# SCore-SR1_2024-11-09.net
KiCad netlist of a schematic drawn in Altium Designer
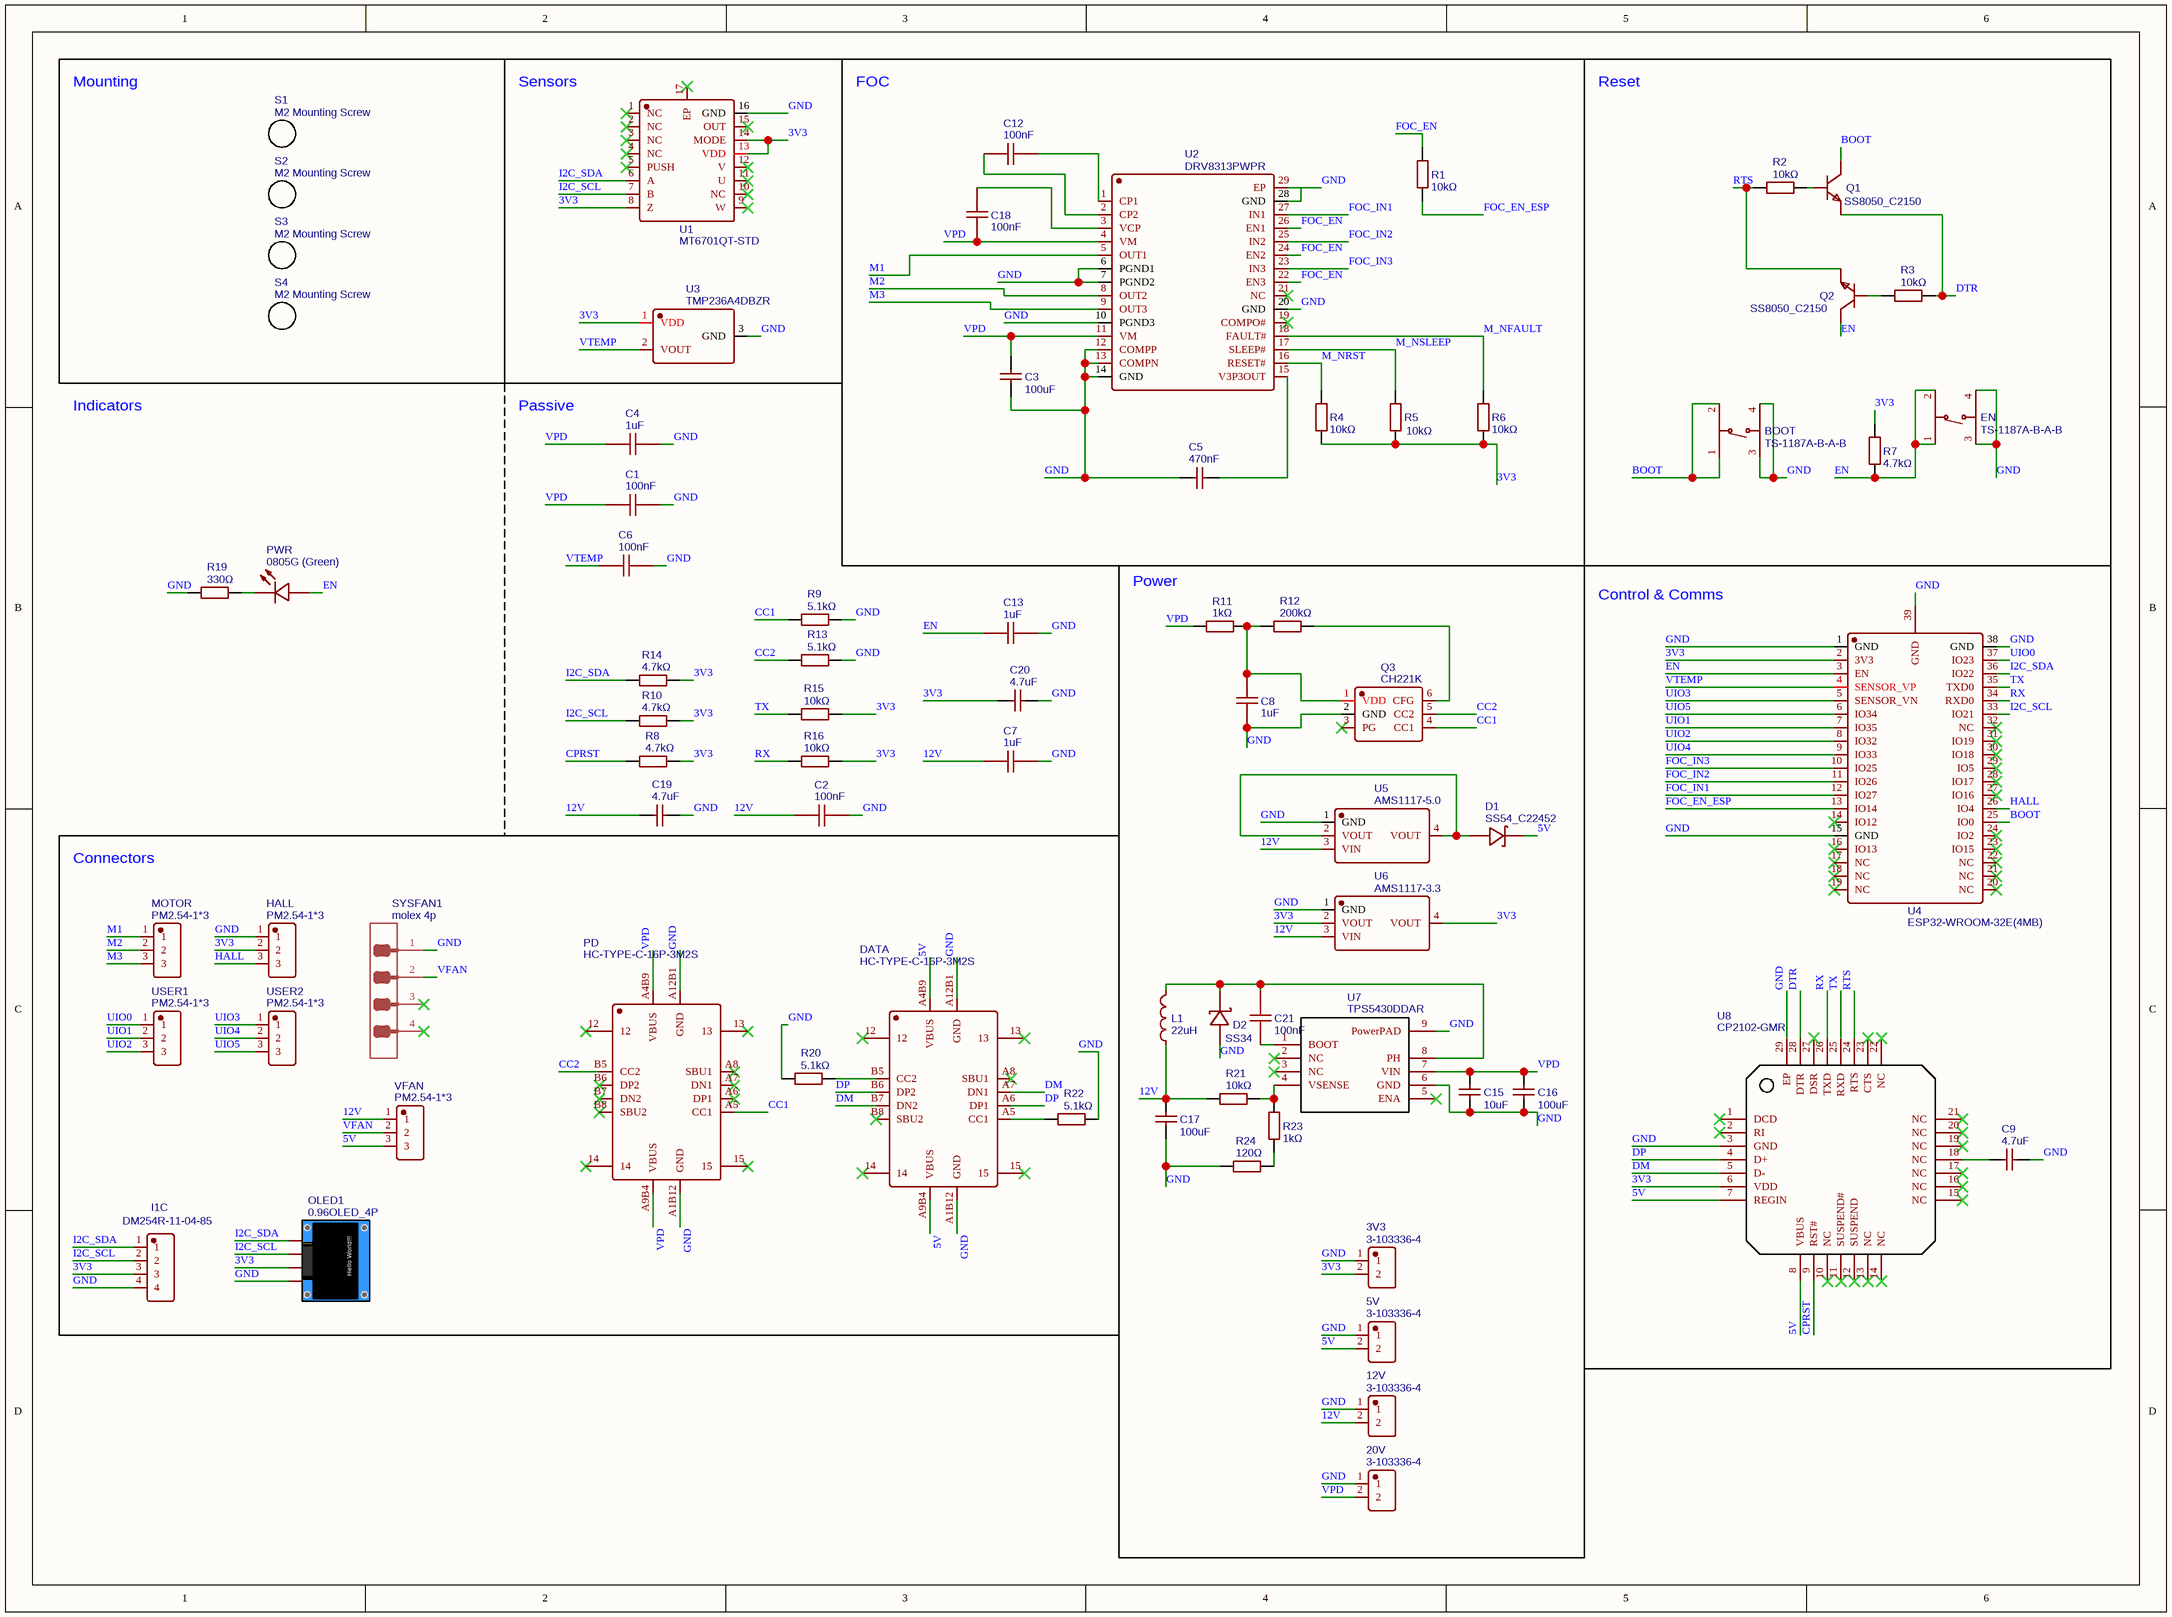
[diagram p0: SCore-SR1_2024-11-09.schdoc]

(export (version "E")
  (design (tool "Eeschema 10.0.6"))
  (components
    (comp (ref "3V3")
      (value "3-103336-4")
      (fields (field (name "MANUFACTURER") "TE Connectivity(泰科电子)") (field (name "CONTRIBUTOR") "lcsc"))
      (libsource (lib "altium-import") (part "root_0_3-103336-4_"))
    )
    (comp (ref "5V")
      (value "3-103336-4")
      (fields (field (name "MANUFACTURER") "TE Connectivity(泰科电子)") (field (name "CONTRIBUTOR") "lcsc"))
      (libsource (lib "altium-import") (part "root_0_3-103336-4_"))
    )
    (comp (ref "12V")
      (value "3-103336-4")
      (fields (field (name "MANUFACTURER") "TE Connectivity(泰科电子)") (field (name "CONTRIBUTOR") "lcsc"))
      (libsource (lib "altium-import") (part "root_0_3-103336-4_"))
    )
    (comp (ref "20V")
      (value "3-103336-4")
      (fields (field (name "MANUFACTURER") "TE Connectivity(泰科电子)") (field (name "CONTRIBUTOR") "lcsc"))
      (libsource (lib "altium-import") (part "root_0_3-103336-4_"))
    )
    (comp (ref "BOOT")
      (value "TS-1187A-B-A-B")
      (fields (field (name "MANUFACTURER") "XKB Connectivity(中国星坤)") (field (name "CONTRIBUTOR") "LCSC"))
      (libsource (lib "altium-import") (part "root_1_TS-1187A-B-A-B_"))
    )
    (comp (ref "C1")
      (value "100nF")
      (fields
        (field (name "MANUFACTURER") "YAGEO(国巨)")
        (field (name "MANUFACTURER PART") "CC0603KRX7R9BB104")
      )
      (libsource (lib "altium-import") (part "root_0_100nF_"))
    )
    (comp (ref "C2")
      (value "100nF")
      (fields
        (field (name "MANUFACTURER") "YAGEO(国巨)")
        (field (name "MANUFACTURER PART") "CC0603KRX7R9BB104")
      )
      (libsource (lib "altium-import") (part "root_0_100nF_"))
    )
    (comp (ref "C3")
      (value "100uF")
      (fields
        (field (name "MANUFACTURER PART") "CL31A107MQHNNNE")
        (field (name "MANUFACTURER") "SAMSUNG(三星)")
      )
      (libsource (lib "altium-import") (part "root_1_100uF_"))
    )
    (comp (ref "C4")
      (value "1uF")
      (fields
        (field (name "MANUFACTURER PART") "CL10A105KB8NNNC")
        (field (name "MANUFACTURER") "SAMSUNG(三星)")
      )
      (libsource (lib "altium-import") (part "root_0_1uF_"))
    )
    (comp (ref "C5")
      (value "470nF")
      (fields
        (field (name "MANUFACTURER PART") "CL21B474KBFNNNE")
        (field (name "MANUFACTURER") "SAMSUNG(三星)")
        (field (name "CONTRIBUTOR") "eisendev")
      )
      (libsource (lib "altium-import") (part "root_3_470nF_"))
    )
    (comp (ref "C6")
      (value "100nF")
      (fields
        (field (name "MANUFACTURER") "YAGEO(国巨)")
        (field (name "MANUFACTURER PART") "CC0603KRX7R9BB104")
      )
      (libsource (lib "altium-import") (part "root_0_100nF_"))
    )
    (comp (ref "C7")
      (value "1uF")
      (fields
        (field (name "MANUFACTURER PART") "CL10A105KB8NNNC")
        (field (name "MANUFACTURER") "SAMSUNG(三星)")
      )
      (libsource (lib "altium-import") (part "root_0_1uF_"))
    )
    (comp (ref "C8")
      (value "1uF")
      (fields
        (field (name "MANUFACTURER PART") "CL10A105KB8NNNC")
        (field (name "MANUFACTURER") "SAMSUNG(三星)")
      )
      (libsource (lib "altium-import") (part "root_1_1uF_"))
    )
    (comp (ref "C9")
      (value "4.7uF")
      (fields
        (field (name "MANUFACTURER PART") "CL21A475KAQNNNE")
        (field (name "MANUFACTURER") "SAMSUNG(三星)")
      )
      (libsource (lib "altium-import") (part "root_0_4.7uF_"))
    )
    (comp (ref "C12")
      (value "100nF")
      (fields
        (field (name "MANUFACTURER") "YAGEO(国巨)")
        (field (name "MANUFACTURER PART") "CC0603KRX7R9BB104")
      )
      (libsource (lib "altium-import") (part "root_0_100nF_"))
    )
    (comp (ref "C13")
      (value "1uF")
      (fields
        (field (name "MANUFACTURER PART") "CL10A105KB8NNNC")
        (field (name "MANUFACTURER") "SAMSUNG(三星)")
      )
      (libsource (lib "altium-import") (part "root_0_1uF_"))
    )
    (comp (ref "C15")
      (value "10uF")
      (fields
        (field (name "MANUFACTURER PART") "CL31A106KBHNNNE")
        (field (name "MANUFACTURER") "SAMSUNG(三星)")
      )
      (libsource (lib "altium-import") (part "root_1_10uF_"))
    )
    (comp (ref "C16")
      (value "100uF")
      (fields
        (field (name "MANUFACTURER PART") "CL31A107MQHNNNE")
        (field (name "MANUFACTURER") "SAMSUNG(三星)")
      )
      (libsource (lib "altium-import") (part "root_1_100uF_"))
    )
    (comp (ref "C17")
      (value "100uF")
      (fields
        (field (name "MANUFACTURER PART") "CL31A107MQHNNNE")
        (field (name "MANUFACTURER") "SAMSUNG(三星)")
      )
      (libsource (lib "altium-import") (part "root_1_100uF_"))
    )
    (comp (ref "C18")
      (value "100nF")
      (fields
        (field (name "MANUFACTURER") "YAGEO(国巨)")
        (field (name "MANUFACTURER PART") "CC0603KRX7R9BB104")
      )
      (libsource (lib "altium-import") (part "root_1_100nF_"))
    )
    (comp (ref "C19")
      (value "4.7uF")
      (fields
        (field (name "MANUFACTURER PART") "CL21A475KAQNNNE")
        (field (name "MANUFACTURER") "SAMSUNG(三星)")
      )
      (libsource (lib "altium-import") (part "root_0_4.7uF_"))
    )
    (comp (ref "C20")
      (value "4.7uF")
      (fields
        (field (name "MANUFACTURER PART") "CL21A475KAQNNNE")
        (field (name "MANUFACTURER") "SAMSUNG(三星)")
      )
      (libsource (lib "altium-import") (part "root_0_4.7uF_"))
    )
    (comp (ref "C21")
      (value "100nF")
      (fields
        (field (name "MANUFACTURER") "YAGEO(国巨)")
        (field (name "MANUFACTURER PART") "CC0603KRX7R9BB104")
      )
      (libsource (lib "altium-import") (part "root_3_100nF_"))
    )
    (comp (ref "D1")
      (value "SS54_C22452")
      (fields
        (field (name "MANUFACTURER PART") "SS54")
        (field (name "MANUFACTURER") "MDD")
        (field (name "CONTRIBUTOR") "mtz8302")
      )
      (libsource (lib "altium-import") (part "root_0_SS54_C22452_"))
    )
    (comp (ref "D2")
      (value "SS34")
      (fields (field (name "MANUFACTURER") "MDD(辰达半导体)"))
      (libsource (lib "altium-import") (part "root_3_SS34_"))
    )
    (comp (ref "DATA")
      (value "HC-TYPE-C-16P-3M2S")
      (fields (field (name "MANUFACTURER") "HC(虹成电子)") (field (name "CONTRIBUTOR") "lcsc"))
      (libsource (lib "altium-import") (part "root_0_HC-TYPE-C-16P-3M2S_"))
    )
    (comp (ref "EN")
      (value "TS-1187A-B-A-B")
      (fields (field (name "MANUFACTURER") "XKB Connectivity(中国星坤)") (field (name "CONTRIBUTOR") "LCSC"))
      (libsource (lib "altium-import") (part "root_1_TS-1187A-B-A-B_"))
    )
    (comp (ref "HALL")
      (value "PM2.54-1*3")
      (fields (field (name "MANUFACTURER") "ZHOURI(洲日)") (field (name "CONTRIBUTOR") "lcsc"))
      (libsource (lib "altium-import") (part "root_0_PM2.54-1*3_"))
    )
    (comp (ref "I1C")
      (value "DM254R-11-04-85")
      (fields (field (name "MANUFACTURER") "DEALON(德艺隆)") (field (name "CONTRIBUTOR") "LCSC"))
      (libsource (lib "altium-import") (part "root_0_DM254R-11-04-85_"))
    )
    (comp (ref "L1")
      (value "22uH")
      (fields (field (name "MANUFACTURER") "FH(风华)") (field (name "MANUFACTURER PART") "PRS4018-220MT"))
      (libsource (lib "altium-import") (part "root_1_22uH_"))
    )
    (comp (ref "MOTOR")
      (value "PM2.54-1*3")
      (fields (field (name "MANUFACTURER") "ZHOURI(洲日)") (field (name "CONTRIBUTOR") "lcsc"))
      (libsource (lib "altium-import") (part "root_0_PM2.54-1*3_"))
    )
    (comp (ref "OLED1")
      (value "0.96OLED_4P")
      (fields (field (name "CONTRIBUTOR") "LCEDA_Lib"))
      (libsource (lib "altium-import") (part "root_3_0.96OLED_4P_"))
    )
    (comp (ref "PD")
      (value "HC-TYPE-C-16P-3M2S")
      (fields (field (name "MANUFACTURER") "HC(虹成电子)") (field (name "CONTRIBUTOR") "lcsc"))
      (libsource (lib "altium-import") (part "root_0_HC-TYPE-C-16P-3M2S_"))
    )
    (comp (ref "PWR")
      (value "0805G (Green)")
      (fields (field (name "MANUFACTURER") "KENTO") (field (name "MANUFACTURER PART") "KT-0805G"))
      (libsource (lib "altium-import") (part "root_0_0805G (Green)_"))
    )
    (comp (ref "Q1")
      (value "SS8050_C2150")
      (fields (field (name "MANUFACTURER") "CJ(江苏长电/长晶)") (field (name "MANUFACTURER PART") "SS8050"))
      (libsource (lib "altium-import") (part "root_0_SS8050_C2150_"))
    )
    (comp (ref "Q2")
      (value "SS8050_C2150")
      (fields (field (name "MANUFACTURER") "CJ(江苏长电/长晶)") (field (name "MANUFACTURER PART") "SS8050"))
      (libsource (lib "altium-import") (part "root_2_SS8050_C2150_"))
    )
    (comp (ref "Q3")
      (value "CH221K")
      (fields (field (name "CONTRIBUTOR") "lcsc"))
      (libsource (lib "altium-import") (part "root_0_CH221K_"))
    )
    (comp (ref "R1")
      (value "10kΩ")
      (fields (field (name "MANUFACTURER") "UniOhm") (field (name "MANUFACTURER PART") "0603WAF4701T5E"))
      (libsource (lib "altium-import") (part "root_1_10kΩ_"))
    )
    (comp (ref "R2")
      (value "10kΩ")
      (fields
        (field (name "MANUFACTURER") "UNI-ROYAL(厚声)")
        (field (name "MANUFACTURER PART") "1206W4F1002T5E")
      )
      (libsource (lib "altium-import") (part "root_0_10kΩ_"))
    )
    (comp (ref "R3")
      (value "10kΩ")
      (fields
        (field (name "MANUFACTURER") "UNI-ROYAL(厚声)")
        (field (name "MANUFACTURER PART") "1206W4F1002T5E")
      )
      (libsource (lib "altium-import") (part "root_0_10kΩ_"))
    )
    (comp (ref "R4")
      (value "10kΩ")
      (fields (field (name "MANUFACTURER") "UniOhm") (field (name "MANUFACTURER PART") "0603WAF4701T5E"))
      (libsource (lib "altium-import") (part "root_1_10kΩ_"))
    )
    (comp (ref "R5")
      (value "10kΩ")
      (fields (field (name "MANUFACTURER") "UniOhm") (field (name "MANUFACTURER PART") "0603WAF4701T5E"))
      (libsource (lib "altium-import") (part "root_1_10kΩ_"))
    )
    (comp (ref "R6")
      (value "10kΩ")
      (fields (field (name "MANUFACTURER") "UniOhm") (field (name "MANUFACTURER PART") "0603WAF4701T5E"))
      (libsource (lib "altium-import") (part "root_1_10kΩ_"))
    )
    (comp (ref "R7")
      (value "4.7kΩ")
      (fields
        (field (name "MANUFACTURER") "UNI-ROYAL(厚声)")
        (field (name "MANUFACTURER PART") "0805W8F4701T5E")
      )
      (libsource (lib "altium-import") (part "root_1_4.7kΩ_"))
    )
    (comp (ref "R8")
      (value "4.7kΩ")
      (fields
        (field (name "MANUFACTURER") "UNI-ROYAL(厚声)")
        (field (name "MANUFACTURER PART") "0805W8F4701T5E")
      )
      (libsource (lib "altium-import") (part "root_2_4.7kΩ_"))
    )
    (comp (ref "R9")
      (value "5.1kΩ")
      (fields
        (field (name "MANUFACTURER PART") "0603WAF5101T5E")
        (field (name "MANUFACTURER") "UNI-ROYAL(厚声)")
      )
      (libsource (lib "altium-import") (part "root_0_5.1kΩ_"))
    )
    (comp (ref "R10")
      (value "4.7kΩ")
      (fields
        (field (name "MANUFACTURER") "UNI-ROYAL(厚声)")
        (field (name "MANUFACTURER PART") "0805W8F4701T5E")
      )
      (libsource (lib "altium-import") (part "root_2_4.7kΩ_"))
    )
    (comp (ref "R11")
      (value "1kΩ")
      (fields
        (field (name "MANUFACTURER") "UNI-ROYAL(厚声)")
        (field (name "MANUFACTURER PART") "0402WGF1001TCE")
      )
      (libsource (lib "altium-import") (part "root_0_1kΩ_"))
    )
    (comp (ref "R12")
      (value "200kΩ")
      (fields
        (field (name "MANUFACTURER") "UNI-ROYAL(厚声)")
        (field (name "MANUFACTURER PART") "0805W8F2003T5E")
      )
      (libsource (lib "altium-import") (part "root_0_200kΩ_"))
    )
    (comp (ref "R13")
      (value "5.1kΩ")
      (fields
        (field (name "MANUFACTURER PART") "0603WAF5101T5E")
        (field (name "MANUFACTURER") "UNI-ROYAL(厚声)")
      )
      (libsource (lib "altium-import") (part "root_0_5.1kΩ_"))
    )
    (comp (ref "R14")
      (value "4.7kΩ")
      (fields
        (field (name "MANUFACTURER") "UNI-ROYAL(厚声)")
        (field (name "MANUFACTURER PART") "0805W8F4701T5E")
      )
      (libsource (lib "altium-import") (part "root_2_4.7kΩ_"))
    )
    (comp (ref "R15")
      (value "10kΩ")
      (fields (field (name "MANUFACTURER") "UniOhm") (field (name "MANUFACTURER PART") "0603WAF4701T5E"))
      (libsource (lib "altium-import") (part "root_2_10kΩ_"))
    )
    (comp (ref "R16")
      (value "10kΩ")
      (fields (field (name "MANUFACTURER") "UniOhm") (field (name "MANUFACTURER PART") "0603WAF4701T5E"))
      (libsource (lib "altium-import") (part "root_2_10kΩ_"))
    )
    (comp (ref "R19")
      (value "330Ω")
      (fields
        (field (name "MANUFACTURER") "UNI-ROYAL(厚声)")
        (field (name "MANUFACTURER PART") "0805W8F3300T5E")
      )
      (libsource (lib "altium-import") (part "root_0_330Ω_"))
    )
    (comp (ref "R20")
      (value "5.1kΩ")
      (fields
        (field (name "MANUFACTURER PART") "0603WAF5101T5E")
        (field (name "MANUFACTURER") "UNI-ROYAL(厚声)")
      )
      (libsource (lib "altium-import") (part "root_0_5.1kΩ_"))
    )
    (comp (ref "R21")
      (value "10kΩ")
      (fields
        (field (name "MANUFACTURER") "UNI-ROYAL(厚声)")
        (field (name "MANUFACTURER PART") "0805W8F1002T5E")
      )
      (libsource (lib "altium-import") (part "root_2_10kΩ_"))
    )
    (comp (ref "R22")
      (value "5.1kΩ")
      (fields
        (field (name "MANUFACTURER PART") "0603WAF5101T5E")
        (field (name "MANUFACTURER") "UNI-ROYAL(厚声)")
      )
      (libsource (lib "altium-import") (part "root_0_5.1kΩ_"))
    )
    (comp (ref "R23")
      (value "1kΩ")
      (fields
        (field (name "MANUFACTURER") "UNI-ROYAL(厚声)")
        (field (name "MANUFACTURER PART") "0402WGF1001TCE")
      )
      (libsource (lib "altium-import") (part "root_1_1kΩ_"))
    )
    (comp (ref "R24")
      (value "120Ω")
      (fields
        (field (name "MANUFACTURER") "UNI-ROYAL(厚声)")
        (field (name "MANUFACTURER PART") "0805W8F1200T5E")
      )
      (libsource (lib "altium-import") (part "root_0_120Ω_"))
    )
    (comp (ref "S1")
      (value "M2 Mounting Screw")
      (fields (field (name "CONTRIBUTOR") "Dayat -"))
      (libsource (lib "altium-import") (part "root_0_M2 Mounting Screw_"))
    )
    (comp (ref "S2")
      (value "M2 Mounting Screw")
      (fields (field (name "CONTRIBUTOR") "Dayat -"))
      (libsource (lib "altium-import") (part "root_0_M2 Mounting Screw_"))
    )
    (comp (ref "S3")
      (value "M2 Mounting Screw")
      (fields (field (name "CONTRIBUTOR") "Dayat -"))
      (libsource (lib "altium-import") (part "root_0_M2 Mounting Screw_"))
    )
    (comp (ref "S4")
      (value "M2 Mounting Screw")
      (fields (field (name "CONTRIBUTOR") "Dayat -"))
      (libsource (lib "altium-import") (part "root_0_M2 Mounting Screw_"))
    )
    (comp (ref "SYSFAN1")
      (value "molex 4p")
      (fields (field (name "CONTRIBUTOR") "delil1220"))
      (libsource (lib "altium-import") (part "root_0_molex 4p_"))
    )
    (comp (ref "U1")
      (value "MT6701QT-STD")
      (fields (field (name "MANUFACTURER") "MagnTek(麦歌恩)") (field (name "CONTRIBUTOR") "LCSC"))
      (libsource (lib "altium-import") (part "root_0_MT6701QT-STD_"))
    )
    (comp (ref "U2")
      (value "DRV8313PWPR")
      (fields (field (name "MANUFACTURER") "Texas Instruments") (field (name "CONTRIBUTOR") "LCSC"))
      (libsource (lib "altium-import") (part "root_0_DRV8313PWPR_"))
    )
    (comp (ref "U3")
      (value "TMP236A4DBZR")
      (fields (field (name "MANUFACTURER") "TI(德州仪器)") (field (name "CONTRIBUTOR") "LCSC"))
      (libsource (lib "altium-import") (part "root_0_TMP236A4DBZR_"))
    )
    (comp (ref "U4")
      (value "ESP32-WROOM-32E(4MB)")
      (fields
        (field (name "MANUFACTURER") "ESPRESSIF(乐鑫)")
        (field (name "MANUFACTURER PART") "ESP32-WROOM-32E-N4")
        (field (name "CONTRIBUTOR") "LCSC")
      )
      (libsource (lib "altium-import") (part "root_0_ESP32-WROOM-32E(4MB)_"))
    )
    (comp (ref "U5")
      (value "AMS1117-5.0")
      (fields (field (name "MANUFACTURER") "AMS"))
      (libsource (lib "altium-import") (part "root_0_AMS1117-5.0_"))
    )
    (comp (ref "U6")
      (value "AMS1117-3.3")
      (fields (field (name "MANUFACTURER") "AMS"))
      (libsource (lib "altium-import") (part "root_0_AMS1117-3.3_"))
    )
    (comp (ref "U7")
      (value "TPS5430DDAR")
      (fields (field (name "MANUFACTURER") "TI(德州仪器)"))
      (libsource (lib "altium-import") (part "root_0_TPS5430DDAR_"))
    )
    (comp (ref "U8")
      (value "CP2102-GMR")
      (fields (field (name "MANUFACTURER") "SKYWORKS/SILICON LABS(芯科)"))
      (libsource (lib "altium-import") (part "root_0_CP2102-GMR_"))
    )
    (comp (ref "USER1")
      (value "PM2.54-1*3")
      (fields (field (name "MANUFACTURER") "ZHOURI(洲日)") (field (name "CONTRIBUTOR") "lcsc"))
      (libsource (lib "altium-import") (part "root_0_PM2.54-1*3_"))
    )
    (comp (ref "USER2")
      (value "PM2.54-1*3")
      (fields (field (name "MANUFACTURER") "ZHOURI(洲日)") (field (name "CONTRIBUTOR") "lcsc"))
      (libsource (lib "altium-import") (part "root_0_PM2.54-1*3_"))
    )
    (comp (ref "VFAN")
      (value "PM2.54-1*3")
      (fields (field (name "MANUFACTURER") "ZHOURI(洲日)") (field (name "CONTRIBUTOR") "lcsc"))
      (libsource (lib "altium-import") (part "root_0_PM2.54-1*3_"))
    )
  )
  (nets
    (net (code "1") (name "/3V3") (class "Default")
      (node (ref "3V3") (pin "2") (pinfunction "2_2") (pintype "passive"))
      (node (ref "C20") (pin "1") (pinfunction "1_1") (pintype "passive"))
      (node (ref "HALL") (pin "2") (pinfunction "2_2") (pintype "passive"))
      (node (ref "I1C") (pin "3") (pinfunction "3_3") (pintype "passive"))
      (node (ref "OLED1") (pin "3") (pinfunction "3_3") (pintype "passive"))
      (node (ref "R10") (pin "1") (pinfunction "1_1") (pintype "passive"))
      (node (ref "R14") (pin "1") (pinfunction "1_1") (pintype "passive"))
      (node (ref "R15") (pin "1") (pinfunction "1_1") (pintype "passive"))
      (node (ref "R16") (pin "1") (pinfunction "1_1") (pintype "passive"))
      (node (ref "R4") (pin "1") (pinfunction "1_1") (pintype "passive"))
      (node (ref "R5") (pin "1") (pinfunction "1_1") (pintype "passive"))
      (node (ref "R6") (pin "1") (pinfunction "1_1") (pintype "passive"))
      (node (ref "R7") (pin "2") (pinfunction "2_2") (pintype "passive"))
      (node (ref "R8") (pin "1") (pinfunction "1_1") (pintype "passive"))
      (node (ref "U1") (pin "13") (pinfunction "VDD_13") (pintype "passive"))
      (node (ref "U1") (pin "14") (pinfunction "MODE_14") (pintype "passive"))
      (node (ref "U1") (pin "8") (pinfunction "Z_8") (pintype "passive"))
      (node (ref "U3") (pin "1") (pinfunction "VDD_1") (pintype "passive"))
      (node (ref "U4") (pin "2") (pinfunction "3V3_2") (pintype "passive"))
      (node (ref "U6") (pin "2") (pinfunction "VOUT_2") (pintype "passive"))
      (node (ref "U6") (pin "4") (pinfunction "VOUT_4") (pintype "passive"))
      (node (ref "U8") (pin "6") (pinfunction "VDD_6") (pintype "passive"))
    )
    (net (code "2") (name "/5V") (class "Default")
      (node (ref "5V") (pin "2") (pinfunction "2_2") (pintype "passive"))
      (node (ref "D1") (pin "2") (pinfunction "K_2") (pintype "passive"))
      (node (ref "DATA") (pin "A4B9") (pinfunction "VBUS_A4B9") (pintype "passive"))
      (node (ref "DATA") (pin "A9B4") (pinfunction "VBUS_A9B4") (pintype "passive"))
      (node (ref "U8") (pin "7") (pinfunction "REGIN_7") (pintype "passive"))
      (node (ref "U8") (pin "8") (pinfunction "VBUS_8") (pintype "passive"))
      (node (ref "VFAN") (pin "3") (pinfunction "3_3") (pintype "passive"))
    )
    (net (code "3") (name "/12V") (class "Default")
      (node (ref "12V") (pin "2") (pinfunction "2_2") (pintype "passive"))
      (node (ref "C17") (pin "2") (pinfunction "2_2") (pintype "passive"))
      (node (ref "C19") (pin "1") (pinfunction "1_1") (pintype "passive"))
      (node (ref "C2") (pin "1") (pinfunction "1_1") (pintype "passive"))
      (node (ref "C7") (pin "1") (pinfunction "1_1") (pintype "passive"))
      (node (ref "L1") (pin "1") (pinfunction "1_1") (pintype "passive"))
      (node (ref "R21") (pin "2") (pinfunction "2_2") (pintype "passive"))
      (node (ref "U5") (pin "3") (pinfunction "VIN_3") (pintype "passive"))
      (node (ref "U6") (pin "3") (pinfunction "VIN_3") (pintype "passive"))
      (node (ref "VFAN") (pin "1") (pinfunction "1_1") (pintype "passive"))
    )
    (net (code "4") (name "/BOOT") (class "Default")
      (node (ref "BOOT") (pin "1") (pinfunction "A_1") (pintype "passive"))
      (node (ref "BOOT") (pin "2") (pinfunction "B_2") (pintype "passive"))
      (node (ref "Q1") (pin "3") (pinfunction "C_3") (pintype "passive"))
      (node (ref "U4") (pin "25") (pinfunction "IO0_25") (pintype "passive"))
    )
    (net (code "5") (name "/CC1") (class "Default")
      (node (ref "PD") (pin "A5") (pinfunction "CC1_A5") (pintype "passive"))
      (node (ref "Q3") (pin "4") (pinfunction "CC1_4") (pintype "passive"))
      (node (ref "R9") (pin "1") (pinfunction "1_1") (pintype "passive"))
    )
    (net (code "6") (name "/CC2") (class "Default")
      (node (ref "PD") (pin "B5") (pinfunction "CC2_B5") (pintype "passive"))
      (node (ref "Q3") (pin "5") (pinfunction "CC2_5") (pintype "passive"))
      (node (ref "R13") (pin "1") (pinfunction "1_1") (pintype "passive"))
    )
    (net (code "7") (name "/CPRST") (class "Default")
      (node (ref "R8") (pin "2") (pinfunction "2_2") (pintype "passive"))
      (node (ref "U8") (pin "9") (pinfunction "RST#_9") (pintype "passive"))
    )
    (net (code "8") (name "/DM") (class "Default")
      (node (ref "DATA") (pin "A7") (pinfunction "DN1_A7") (pintype "passive"))
      (node (ref "DATA") (pin "B7") (pinfunction "DN2_B7") (pintype "passive"))
      (node (ref "U8") (pin "5") (pinfunction "D-_5") (pintype "passive"))
    )
    (net (code "9") (name "/DP") (class "Default")
      (node (ref "DATA") (pin "A6") (pinfunction "DP1_A6") (pintype "passive"))
      (node (ref "DATA") (pin "B6") (pinfunction "DP2_B6") (pintype "passive"))
      (node (ref "U8") (pin "4") (pinfunction "D+_4") (pintype "passive"))
    )
    (net (code "10") (name "/DTR") (class "Default")
      (node (ref "Q1") (pin "2") (pinfunction "E_2") (pintype "passive"))
      (node (ref "R3") (pin "2") (pinfunction "2_2") (pintype "passive"))
      (node (ref "U8") (pin "28") (pinfunction "DTR_28") (pintype "passive"))
    )
    (net (code "11") (name "/EN") (class "Default")
      (node (ref "C13") (pin "1") (pinfunction "1_1") (pintype "passive"))
      (node (ref "EN") (pin "1") (pinfunction "A_1") (pintype "passive"))
      (node (ref "EN") (pin "2") (pinfunction "B_2") (pintype "passive"))
      (node (ref "PWR") (pin "1") (pinfunction "A_1") (pintype "passive"))
      (node (ref "Q2") (pin "3") (pinfunction "C_3") (pintype "passive"))
      (node (ref "R7") (pin "1") (pinfunction "1_1") (pintype "passive"))
      (node (ref "U4") (pin "3") (pinfunction "EN_3") (pintype "passive"))
    )
    (net (code "12") (name "/FOC_EN") (class "Default")
      (node (ref "R1") (pin "2") (pinfunction "2_2") (pintype "passive"))
      (node (ref "U2") (pin "22") (pinfunction "EN3_22") (pintype "passive"))
      (node (ref "U2") (pin "24") (pinfunction "EN2_24") (pintype "passive"))
      (node (ref "U2") (pin "26") (pinfunction "EN1_26") (pintype "passive"))
    )
    (net (code "13") (name "/FOC_EN_ESP") (class "Default")
      (node (ref "R1") (pin "1") (pinfunction "1_1") (pintype "passive"))
      (node (ref "U4") (pin "13") (pinfunction "IO14_13") (pintype "passive"))
    )
    (net (code "14") (name "/FOC_IN1") (class "Default")
      (node (ref "U2") (pin "27") (pinfunction "IN1_27") (pintype "passive"))
      (node (ref "U4") (pin "12") (pinfunction "IO27_12") (pintype "passive"))
    )
    (net (code "15") (name "/FOC_IN2") (class "Default")
      (node (ref "U2") (pin "25") (pinfunction "IN2_25") (pintype "passive"))
      (node (ref "U4") (pin "11") (pinfunction "IO26_11") (pintype "passive"))
    )
    (net (code "16") (name "/FOC_IN3") (class "Default")
      (node (ref "U2") (pin "23") (pinfunction "IN3_23") (pintype "passive"))
      (node (ref "U4") (pin "10") (pinfunction "IO25_10") (pintype "passive"))
    )
    (net (code "17") (name "/GND") (class "Default")
      (node (ref "12V") (pin "1") (pinfunction "1_1") (pintype "passive"))
      (node (ref "20V") (pin "1") (pinfunction "1_1") (pintype "passive"))
      (node (ref "3V3") (pin "1") (pinfunction "1_1") (pintype "passive"))
      (node (ref "5V") (pin "1") (pinfunction "1_1") (pintype "passive"))
      (node (ref "BOOT") (pin "3") (pinfunction "C_3") (pintype "passive"))
      (node (ref "BOOT") (pin "4") (pinfunction "D_4") (pintype "passive"))
      (node (ref "C1") (pin "2") (pinfunction "2_2") (pintype "passive"))
      (node (ref "C13") (pin "2") (pinfunction "2_2") (pintype "passive"))
      (node (ref "C15") (pin "1") (pinfunction "1_1") (pintype "passive"))
      (node (ref "C16") (pin "1") (pinfunction "1_1") (pintype "passive"))
      (node (ref "C17") (pin "1") (pinfunction "1_1") (pintype "passive"))
      (node (ref "C19") (pin "2") (pinfunction "2_2") (pintype "passive"))
      (node (ref "C2") (pin "2") (pinfunction "2_2") (pintype "passive"))
      (node (ref "C20") (pin "2") (pinfunction "2_2") (pintype "passive"))
      (node (ref "C3") (pin "1") (pinfunction "1_1") (pintype "passive"))
      (node (ref "C4") (pin "2") (pinfunction "2_2") (pintype "passive"))
      (node (ref "C5") (pin "1") (pinfunction "1_1") (pintype "passive"))
      (node (ref "C6") (pin "2") (pinfunction "2_2") (pintype "passive"))
      (node (ref "C7") (pin "2") (pinfunction "2_2") (pintype "passive"))
      (node (ref "C8") (pin "1") (pinfunction "1_1") (pintype "passive"))
      (node (ref "C9") (pin "2") (pinfunction "2_2") (pintype "passive"))
      (node (ref "D2") (pin "2") (pinfunction "A_2") (pintype "passive"))
      (node (ref "DATA") (pin "A12B1") (pinfunction "GND_A12B1") (pintype "passive"))
      (node (ref "DATA") (pin "A1B12") (pinfunction "GND_A1B12") (pintype "passive"))
      (node (ref "EN") (pin "3") (pinfunction "C_3") (pintype "passive"))
      (node (ref "EN") (pin "4") (pinfunction "D_4") (pintype "passive"))
      (node (ref "HALL") (pin "1") (pinfunction "1_1") (pintype "passive"))
      (node (ref "I1C") (pin "4") (pinfunction "4_4") (pintype "passive"))
      (node (ref "OLED1") (pin "4") (pinfunction "4_4") (pintype "passive"))
      (node (ref "PD") (pin "A12B1") (pinfunction "GND_A12B1") (pintype "passive"))
      (node (ref "PD") (pin "A1B12") (pinfunction "GND_A1B12") (pintype "passive"))
      (node (ref "Q3") (pin "2") (pinfunction "GND_2") (pintype "passive"))
      (node (ref "R13") (pin "2") (pinfunction "2_2") (pintype "passive"))
      (node (ref "R19") (pin "1") (pinfunction "1_1") (pintype "passive"))
      (node (ref "R20") (pin "1") (pinfunction "1_1") (pintype "passive"))
      (node (ref "R22") (pin "2") (pinfunction "2_2") (pintype "passive"))
      (node (ref "R24") (pin "1") (pinfunction "1_1") (pintype "passive"))
      (node (ref "R9") (pin "2") (pinfunction "2_2") (pintype "passive"))
      (node (ref "SYSFAN1") (pin "1") (pinfunction "1_1") (pintype "passive"))
      (node (ref "U1") (pin "16") (pinfunction "GND_16") (pintype "passive"))
      (node (ref "U2") (pin "10") (pinfunction "PGND3_10") (pintype "passive"))
      (node (ref "U2") (pin "12") (pinfunction "COMPP_12") (pintype "passive"))
      (node (ref "U2") (pin "13") (pinfunction "COMPN_13") (pintype "passive"))
      (node (ref "U2") (pin "14") (pinfunction "GND_14") (pintype "passive"))
      (node (ref "U2") (pin "20") (pinfunction "GND_20") (pintype "passive"))
      (node (ref "U2") (pin "28") (pinfunction "GND_28") (pintype "passive"))
      (node (ref "U2") (pin "29") (pinfunction "EP_29") (pintype "passive"))
      (node (ref "U2") (pin "6") (pinfunction "PGND1_6") (pintype "passive"))
      (node (ref "U2") (pin "7") (pinfunction "PGND2_7") (pintype "passive"))
      (node (ref "U3") (pin "3") (pinfunction "GND_3") (pintype "passive"))
      (node (ref "U4") (pin "1") (pinfunction "GND_1") (pintype "passive"))
      (node (ref "U4") (pin "15") (pinfunction "GND_15") (pintype "passive"))
      (node (ref "U4") (pin "38") (pinfunction "GND_38") (pintype "passive"))
      (node (ref "U4") (pin "39") (pinfunction "GND_39") (pintype "passive"))
      (node (ref "U5") (pin "1") (pinfunction "GND_1") (pintype "passive"))
      (node (ref "U6") (pin "1") (pinfunction "GND_1") (pintype "passive"))
      (node (ref "U7") (pin "6") (pinfunction "GND_6") (pintype "passive"))
      (node (ref "U7") (pin "9") (pinfunction "PowerPAD_9") (pintype "passive"))
      (node (ref "U8") (pin "29") (pinfunction "EP_29") (pintype "passive"))
      (node (ref "U8") (pin "3") (pinfunction "GND_3") (pintype "passive"))
    )
    (net (code "18") (name "/HALL") (class "Default")
      (node (ref "HALL") (pin "3") (pinfunction "3_3") (pintype "passive"))
      (node (ref "U4") (pin "26") (pinfunction "IO4_26") (pintype "passive"))
    )
    (net (code "19") (name "/I2C_SCL") (class "Default")
      (node (ref "I1C") (pin "2") (pinfunction "2_2") (pintype "passive"))
      (node (ref "OLED1") (pin "2") (pinfunction "2_2") (pintype "passive"))
      (node (ref "R10") (pin "2") (pinfunction "2_2") (pintype "passive"))
      (node (ref "U1") (pin "7") (pinfunction "B_7") (pintype "passive"))
      (node (ref "U4") (pin "33") (pinfunction "IO21_33") (pintype "passive"))
    )
    (net (code "20") (name "/I2C_SDA") (class "Default")
      (node (ref "I1C") (pin "1") (pinfunction "1_1") (pintype "passive"))
      (node (ref "OLED1") (pin "1") (pinfunction "1_1") (pintype "passive"))
      (node (ref "R14") (pin "2") (pinfunction "2_2") (pintype "passive"))
      (node (ref "U1") (pin "6") (pinfunction "A_6") (pintype "passive"))
      (node (ref "U4") (pin "36") (pinfunction "IO22_36") (pintype "passive"))
    )
    (net (code "21") (name "/M1") (class "Default")
      (node (ref "MOTOR") (pin "1") (pinfunction "1_1") (pintype "passive"))
      (node (ref "U2") (pin "5") (pinfunction "OUT1_5") (pintype "passive"))
    )
    (net (code "22") (name "/M2") (class "Default")
      (node (ref "MOTOR") (pin "2") (pinfunction "2_2") (pintype "passive"))
      (node (ref "U2") (pin "8") (pinfunction "OUT2_8") (pintype "passive"))
    )
    (net (code "23") (name "/M3") (class "Default")
      (node (ref "MOTOR") (pin "3") (pinfunction "3_3") (pintype "passive"))
      (node (ref "U2") (pin "9") (pinfunction "OUT3_9") (pintype "passive"))
    )
    (net (code "24") (name "/M_NFAULT") (class "Default")
      (node (ref "R6") (pin "2") (pinfunction "2_2") (pintype "passive"))
      (node (ref "U2") (pin "18") (pinfunction "FAULT#_18") (pintype "passive"))
    )
    (net (code "25") (name "/M_NRST") (class "Default")
      (node (ref "R4") (pin "2") (pinfunction "2_2") (pintype "passive"))
      (node (ref "U2") (pin "16") (pinfunction "RESET#_16") (pintype "passive"))
    )
    (net (code "26") (name "/M_NSLEEP") (class "Default")
      (node (ref "R5") (pin "2") (pinfunction "2_2") (pintype "passive"))
      (node (ref "U2") (pin "17") (pinfunction "SLEEP#_17") (pintype "passive"))
    )
    (net (code "27") (name "/RTS") (class "Default")
      (node (ref "Q2") (pin "2") (pinfunction "E_2") (pintype "passive"))
      (node (ref "R2") (pin "1") (pinfunction "1_1") (pintype "passive"))
      (node (ref "U8") (pin "24") (pinfunction "RTS_24") (pintype "passive"))
    )
    (net (code "28") (name "/RX") (class "Default")
      (node (ref "R16") (pin "2") (pinfunction "2_2") (pintype "passive"))
      (node (ref "U4") (pin "34") (pinfunction "RXD0_34") (pintype "passive"))
      (node (ref "U8") (pin "26") (pinfunction "TXD_26") (pintype "passive"))
    )
    (net (code "29") (name "/TX") (class "Default")
      (node (ref "R15") (pin "2") (pinfunction "2_2") (pintype "passive"))
      (node (ref "U4") (pin "35") (pinfunction "TXD0_35") (pintype "passive"))
      (node (ref "U8") (pin "25") (pinfunction "RXD_25") (pintype "passive"))
    )
    (net (code "30") (name "/UIO0") (class "Default")
      (node (ref "U4") (pin "37") (pinfunction "IO23_37") (pintype "passive"))
      (node (ref "USER1") (pin "1") (pinfunction "1_1") (pintype "passive"))
    )
    (net (code "31") (name "/UIO1") (class "Default")
      (node (ref "U4") (pin "7") (pinfunction "IO35_7") (pintype "passive"))
      (node (ref "USER1") (pin "2") (pinfunction "2_2") (pintype "passive"))
    )
    (net (code "32") (name "/UIO2") (class "Default")
      (node (ref "U4") (pin "8") (pinfunction "IO32_8") (pintype "passive"))
      (node (ref "USER1") (pin "3") (pinfunction "3_3") (pintype "passive"))
    )
    (net (code "33") (name "/UIO3") (class "Default")
      (node (ref "U4") (pin "5") (pinfunction "SENSOR_VN_5") (pintype "passive"))
      (node (ref "USER2") (pin "1") (pinfunction "1_1") (pintype "passive"))
    )
    (net (code "34") (name "/UIO4") (class "Default")
      (node (ref "U4") (pin "9") (pinfunction "IO33_9") (pintype "passive"))
      (node (ref "USER2") (pin "2") (pinfunction "2_2") (pintype "passive"))
    )
    (net (code "35") (name "/UIO5") (class "Default")
      (node (ref "U4") (pin "6") (pinfunction "IO34_6") (pintype "passive"))
      (node (ref "USER2") (pin "3") (pinfunction "3_3") (pintype "passive"))
    )
    (net (code "36") (name "/VFAN") (class "Default")
      (node (ref "SYSFAN1") (pin "2") (pinfunction "2_2") (pintype "passive"))
      (node (ref "VFAN") (pin "2") (pinfunction "2_2") (pintype "passive"))
    )
    (net (code "37") (name "/VPD") (class "Default")
      (node (ref "20V") (pin "2") (pinfunction "2_2") (pintype "passive"))
      (node (ref "C1") (pin "1") (pinfunction "1_1") (pintype "passive"))
      (node (ref "C15") (pin "2") (pinfunction "2_2") (pintype "passive"))
      (node (ref "C16") (pin "2") (pinfunction "2_2") (pintype "passive"))
      (node (ref "C18") (pin "1") (pinfunction "1_1") (pintype "passive"))
      (node (ref "C3") (pin "2") (pinfunction "2_2") (pintype "passive"))
      (node (ref "C4") (pin "1") (pinfunction "1_1") (pintype "passive"))
      (node (ref "PD") (pin "A4B9") (pinfunction "VBUS_A4B9") (pintype "passive"))
      (node (ref "PD") (pin "A9B4") (pinfunction "VBUS_A9B4") (pintype "passive"))
      (node (ref "R11") (pin "1") (pinfunction "1_1") (pintype "passive"))
      (node (ref "U2") (pin "11") (pinfunction "VM_11") (pintype "passive"))
      (node (ref "U2") (pin "4") (pinfunction "VM_4") (pintype "passive"))
      (node (ref "U7") (pin "7") (pinfunction "VIN_7") (pintype "passive"))
    )
    (net (code "38") (name "/VTEMP") (class "Default")
      (node (ref "C6") (pin "1") (pinfunction "1_1") (pintype "passive"))
      (node (ref "U3") (pin "2") (pinfunction "VOUT_2") (pintype "passive"))
      (node (ref "U4") (pin "4") (pinfunction "SENSOR_VP_4") (pintype "passive"))
    )
    (net (code "39") (name "Net-(C9-Pad1)") (class "Default")
      (node (ref "C9") (pin "1") (pinfunction "1_1") (pintype "passive"))
      (node (ref "U8") (pin "18") (pinfunction "NC_18") (pintype "passive"))
    )
    (net (code "40") (name "Net-(D1-A)") (class "Default")
      (node (ref "D1") (pin "1") (pinfunction "A_1") (pintype "passive"))
      (node (ref "U5") (pin "2") (pinfunction "VOUT_2") (pintype "passive"))
      (node (ref "U5") (pin "4") (pinfunction "VOUT_4") (pintype "passive"))
    )
    (net (code "41") (name "Net-(D2-K)") (class "Default")
      (node (ref "C21") (pin "1") (pinfunction "1_1") (pintype "passive"))
      (node (ref "D2") (pin "1") (pinfunction "K_1") (pintype "passive"))
      (node (ref "L1") (pin "2") (pinfunction "2_2") (pintype "passive"))
      (node (ref "U7") (pin "8") (pinfunction "PH_8") (pintype "passive"))
    )
    (net (code "42") (name "Net-(DATA-CC1)") (class "Default")
      (node (ref "DATA") (pin "A5") (pinfunction "CC1_A5") (pintype "passive"))
      (node (ref "R22") (pin "1") (pinfunction "1_1") (pintype "passive"))
    )
    (net (code "43") (name "Net-(DATA-CC2)") (class "Default")
      (node (ref "DATA") (pin "B5") (pinfunction "CC2_B5") (pintype "passive"))
      (node (ref "R20") (pin "2") (pinfunction "2_2") (pintype "passive"))
    )
    (net (code "44") (name "Net-(PWR-K)") (class "Default")
      (node (ref "PWR") (pin "2") (pinfunction "K_2") (pintype "passive"))
      (node (ref "R19") (pin "2") (pinfunction "2_2") (pintype "passive"))
    )
    (net (code "45") (name "Net-(Q1-B)") (class "Default")
      (node (ref "Q1") (pin "1") (pinfunction "B_1") (pintype "passive"))
      (node (ref "R2") (pin "2") (pinfunction "2_2") (pintype "passive"))
    )
    (net (code "46") (name "Net-(Q2-B)") (class "Default")
      (node (ref "Q2") (pin "1") (pinfunction "B_1") (pintype "passive"))
      (node (ref "R3") (pin "1") (pinfunction "1_1") (pintype "passive"))
    )
    (net (code "47") (name "Net-(Q3-CFG)") (class "Default")
      (node (ref "Q3") (pin "6") (pinfunction "CFG_6") (pintype "passive"))
      (node (ref "R12") (pin "2") (pinfunction "2_2") (pintype "passive"))
    )
    (net (code "48") (name "Net-(Q3-VDD)") (class "Default")
      (node (ref "C8") (pin "2") (pinfunction "2_2") (pintype "passive"))
      (node (ref "Q3") (pin "1") (pinfunction "VDD_1") (pintype "passive"))
      (node (ref "R11") (pin "2") (pinfunction "2_2") (pintype "passive"))
      (node (ref "R12") (pin "1") (pinfunction "1_1") (pintype "passive"))
    )
    (net (code "49") (name "Net-(R23-Pad1)") (class "Default")
      (node (ref "R23") (pin "1") (pinfunction "1_1") (pintype "passive"))
      (node (ref "R24") (pin "2") (pinfunction "2_2") (pintype "passive"))
    )
    (net (code "50") (name "Net-(U2-CP1)") (class "Default")
      (node (ref "C12") (pin "2") (pinfunction "2_2") (pintype "passive"))
      (node (ref "U2") (pin "1") (pinfunction "CP1_1") (pintype "passive"))
    )
    (net (code "51") (name "Net-(U2-CP2)") (class "Default")
      (node (ref "C12") (pin "1") (pinfunction "1_1") (pintype "passive"))
      (node (ref "U2") (pin "2") (pinfunction "CP2_2") (pintype "passive"))
    )
    (net (code "52") (name "Net-(U2-V3P3OUT)") (class "Default")
      (node (ref "C5") (pin "2") (pinfunction "2_2") (pintype "passive"))
      (node (ref "U2") (pin "15") (pinfunction "V3P3OUT_15") (pintype "passive"))
    )
    (net (code "53") (name "Net-(U2-VCP)") (class "Default")
      (node (ref "C18") (pin "2") (pinfunction "2_2") (pintype "passive"))
      (node (ref "U2") (pin "3") (pinfunction "VCP_3") (pintype "passive"))
    )
    (net (code "54") (name "Net-(U7-BOOT)") (class "Default")
      (node (ref "C21") (pin "2") (pinfunction "2_2") (pintype "passive"))
      (node (ref "U7") (pin "1") (pinfunction "BOOT_1") (pintype "passive"))
    )
    (net (code "55") (name "Net-(U7-VSENSE)") (class "Default")
      (node (ref "R21") (pin "1") (pinfunction "1_1") (pintype "passive"))
      (node (ref "R23") (pin "2") (pinfunction "2_2") (pintype "passive"))
      (node (ref "U7") (pin "4") (pinfunction "VSENSE_4") (pintype "passive"))
    )
    (net (code "56") (name "unconnected-(DATA-Pad12)") (class "Default")
      (node (ref "DATA") (pin "12") (pinfunction "12_12") (pintype "passive+no_connect"))
    )
    (net (code "57") (name "unconnected-(DATA-Pad13)") (class "Default")
      (node (ref "DATA") (pin "13") (pinfunction "13_13") (pintype "passive+no_connect"))
    )
    (net (code "58") (name "unconnected-(DATA-Pad14)") (class "Default")
      (node (ref "DATA") (pin "14") (pinfunction "14_14") (pintype "passive+no_connect"))
    )
    (net (code "59") (name "unconnected-(DATA-Pad15)") (class "Default")
      (node (ref "DATA") (pin "15") (pinfunction "15_15") (pintype "passive+no_connect"))
    )
    (net (code "60") (name "unconnected-(DATA-SBU1-PadA8)") (class "Default")
      (node (ref "DATA") (pin "A8") (pinfunction "SBU1_A8") (pintype "passive+no_connect"))
    )
    (net (code "61") (name "unconnected-(DATA-SBU2-PadB8)") (class "Default")
      (node (ref "DATA") (pin "B8") (pinfunction "SBU2_B8") (pintype "passive+no_connect"))
    )
    (net (code "62") (name "unconnected-(PD-DN1-PadA7)") (class "Default")
      (node (ref "PD") (pin "A7") (pinfunction "DN1_A7") (pintype "passive+no_connect"))
    )
    (net (code "63") (name "unconnected-(PD-DN2-PadB7)") (class "Default")
      (node (ref "PD") (pin "B7") (pinfunction "DN2_B7") (pintype "passive+no_connect"))
    )
    (net (code "64") (name "unconnected-(PD-DP1-PadA6)") (class "Default")
      (node (ref "PD") (pin "A6") (pinfunction "DP1_A6") (pintype "passive+no_connect"))
    )
    (net (code "65") (name "unconnected-(PD-DP2-PadB6)") (class "Default")
      (node (ref "PD") (pin "B6") (pinfunction "DP2_B6") (pintype "passive+no_connect"))
    )
    (net (code "66") (name "unconnected-(PD-Pad12)") (class "Default")
      (node (ref "PD") (pin "12") (pinfunction "12_12") (pintype "passive+no_connect"))
    )
    (net (code "67") (name "unconnected-(PD-Pad13)") (class "Default")
      (node (ref "PD") (pin "13") (pinfunction "13_13") (pintype "passive+no_connect"))
    )
    (net (code "68") (name "unconnected-(PD-Pad14)") (class "Default")
      (node (ref "PD") (pin "14") (pinfunction "14_14") (pintype "passive+no_connect"))
    )
    (net (code "69") (name "unconnected-(PD-Pad15)") (class "Default")
      (node (ref "PD") (pin "15") (pinfunction "15_15") (pintype "passive+no_connect"))
    )
    (net (code "70") (name "unconnected-(PD-SBU1-PadA8)") (class "Default")
      (node (ref "PD") (pin "A8") (pinfunction "SBU1_A8") (pintype "passive+no_connect"))
    )
    (net (code "71") (name "unconnected-(PD-SBU2-PadB8)") (class "Default")
      (node (ref "PD") (pin "B8") (pinfunction "SBU2_B8") (pintype "passive+no_connect"))
    )
    (net (code "72") (name "unconnected-(Q3-PG-Pad3)") (class "Default")
      (node (ref "Q3") (pin "3") (pinfunction "PG_3") (pintype "passive+no_connect"))
    )
    (net (code "73") (name "unconnected-(SYSFAN1-Pad3)") (class "Default")
      (node (ref "SYSFAN1") (pin "3") (pinfunction "3_3") (pintype "passive+no_connect"))
    )
    (net (code "74") (name "unconnected-(SYSFAN1-Pad4)") (class "Default")
      (node (ref "SYSFAN1") (pin "4") (pinfunction "4_4") (pintype "passive+no_connect"))
    )
    (net (code "75") (name "unconnected-(U1-EP-Pad17)") (class "Default")
      (node (ref "U1") (pin "17") (pinfunction "EP_17") (pintype "passive+no_connect"))
    )
    (net (code "76") (name "unconnected-(U1-NC-Pad1)") (class "Default")
      (node (ref "U1") (pin "1") (pinfunction "NC_1") (pintype "passive+no_connect"))
    )
    (net (code "77") (name "unconnected-(U1-NC-Pad2)") (class "Default")
      (node (ref "U1") (pin "2") (pinfunction "NC_2") (pintype "passive+no_connect"))
    )
    (net (code "78") (name "unconnected-(U1-NC-Pad3)") (class "Default")
      (node (ref "U1") (pin "3") (pinfunction "NC_3") (pintype "passive+no_connect"))
    )
    (net (code "79") (name "unconnected-(U1-NC-Pad4)") (class "Default")
      (node (ref "U1") (pin "4") (pinfunction "NC_4") (pintype "passive+no_connect"))
    )
    (net (code "80") (name "unconnected-(U1-NC-Pad10)") (class "Default")
      (node (ref "U1") (pin "10") (pinfunction "NC_10") (pintype "passive+no_connect"))
    )
    (net (code "81") (name "unconnected-(U1-OUT-Pad15)") (class "Default")
      (node (ref "U1") (pin "15") (pinfunction "OUT_15") (pintype "passive+no_connect"))
    )
    (net (code "82") (name "unconnected-(U1-PUSH-Pad5)") (class "Default")
      (node (ref "U1") (pin "5") (pinfunction "PUSH_5") (pintype "passive+no_connect"))
    )
    (net (code "83") (name "unconnected-(U1-U-Pad11)") (class "Default")
      (node (ref "U1") (pin "11") (pinfunction "U_11") (pintype "passive+no_connect"))
    )
    (net (code "84") (name "unconnected-(U1-V-Pad12)") (class "Default")
      (node (ref "U1") (pin "12") (pinfunction "V_12") (pintype "passive+no_connect"))
    )
    (net (code "85") (name "unconnected-(U1-W-Pad9)") (class "Default")
      (node (ref "U1") (pin "9") (pinfunction "W_9") (pintype "passive+no_connect"))
    )
    (net (code "86") (name "unconnected-(U2-COMPO#-Pad19)") (class "Default")
      (node (ref "U2") (pin "19") (pinfunction "COMPO#_19") (pintype "passive+no_connect"))
    )
    (net (code "87") (name "unconnected-(U2-NC-Pad21)") (class "Default")
      (node (ref "U2") (pin "21") (pinfunction "NC_21") (pintype "passive+no_connect"))
    )
    (net (code "88") (name "unconnected-(U4-IO2-Pad24)") (class "Default")
      (node (ref "U4") (pin "24") (pinfunction "IO2_24") (pintype "passive+no_connect"))
    )
    (net (code "89") (name "unconnected-(U4-IO5-Pad29)") (class "Default")
      (node (ref "U4") (pin "29") (pinfunction "IO5_29") (pintype "passive+no_connect"))
    )
    (net (code "90") (name "unconnected-(U4-IO12-Pad14)") (class "Default")
      (node (ref "U4") (pin "14") (pinfunction "IO12_14") (pintype "passive+no_connect"))
    )
    (net (code "91") (name "unconnected-(U4-IO13-Pad16)") (class "Default")
      (node (ref "U4") (pin "16") (pinfunction "IO13_16") (pintype "passive+no_connect"))
    )
    (net (code "92") (name "unconnected-(U4-IO15-Pad23)") (class "Default")
      (node (ref "U4") (pin "23") (pinfunction "IO15_23") (pintype "passive+no_connect"))
    )
    (net (code "93") (name "unconnected-(U4-IO16-Pad27)") (class "Default")
      (node (ref "U4") (pin "27") (pinfunction "IO16_27") (pintype "passive+no_connect"))
    )
    (net (code "94") (name "unconnected-(U4-IO17-Pad28)") (class "Default")
      (node (ref "U4") (pin "28") (pinfunction "IO17_28") (pintype "passive+no_connect"))
    )
    (net (code "95") (name "unconnected-(U4-IO18-Pad30)") (class "Default")
      (node (ref "U4") (pin "30") (pinfunction "IO18_30") (pintype "passive+no_connect"))
    )
    (net (code "96") (name "unconnected-(U4-IO19-Pad31)") (class "Default")
      (node (ref "U4") (pin "31") (pinfunction "IO19_31") (pintype "passive+no_connect"))
    )
    (net (code "97") (name "unconnected-(U4-NC-Pad17)") (class "Default")
      (node (ref "U4") (pin "17") (pinfunction "NC_17") (pintype "passive+no_connect"))
    )
    (net (code "98") (name "unconnected-(U4-NC-Pad18)") (class "Default")
      (node (ref "U4") (pin "18") (pinfunction "NC_18") (pintype "passive+no_connect"))
    )
    (net (code "99") (name "unconnected-(U4-NC-Pad19)") (class "Default")
      (node (ref "U4") (pin "19") (pinfunction "NC_19") (pintype "passive+no_connect"))
    )
    (net (code "100") (name "unconnected-(U4-NC-Pad20)") (class "Default")
      (node (ref "U4") (pin "20") (pinfunction "NC_20") (pintype "passive+no_connect"))
    )
    (net (code "101") (name "unconnected-(U4-NC-Pad21)") (class "Default")
      (node (ref "U4") (pin "21") (pinfunction "NC_21") (pintype "passive+no_connect"))
    )
    (net (code "102") (name "unconnected-(U4-NC-Pad22)") (class "Default")
      (node (ref "U4") (pin "22") (pinfunction "NC_22") (pintype "passive+no_connect"))
    )
    (net (code "103") (name "unconnected-(U4-NC-Pad32)") (class "Default")
      (node (ref "U4") (pin "32") (pinfunction "NC_32") (pintype "passive+no_connect"))
    )
    (net (code "104") (name "unconnected-(U7-ENA-Pad5)") (class "Default")
      (node (ref "U7") (pin "5") (pinfunction "ENA_5") (pintype "passive+no_connect"))
    )
    (net (code "105") (name "unconnected-(U7-NC-Pad2)") (class "Default")
      (node (ref "U7") (pin "2") (pinfunction "NC_2") (pintype "passive+no_connect"))
    )
    (net (code "106") (name "unconnected-(U7-NC-Pad3)") (class "Default")
      (node (ref "U7") (pin "3") (pinfunction "NC_3") (pintype "passive+no_connect"))
    )
    (net (code "107") (name "unconnected-(U8-CTS-Pad23)") (class "Default")
      (node (ref "U8") (pin "23") (pinfunction "CTS_23") (pintype "passive+no_connect"))
    )
    (net (code "108") (name "unconnected-(U8-DCD-Pad1)") (class "Default")
      (node (ref "U8") (pin "1") (pinfunction "DCD_1") (pintype "passive+no_connect"))
    )
    (net (code "109") (name "unconnected-(U8-DSR-Pad27)") (class "Default")
      (node (ref "U8") (pin "27") (pinfunction "DSR_27") (pintype "passive+no_connect"))
    )
    (net (code "110") (name "unconnected-(U8-NC-Pad10)") (class "Default")
      (node (ref "U8") (pin "10") (pinfunction "NC_10") (pintype "passive+no_connect"))
    )
    (net (code "111") (name "unconnected-(U8-NC-Pad13)") (class "Default")
      (node (ref "U8") (pin "13") (pinfunction "NC_13") (pintype "passive+no_connect"))
    )
    (net (code "112") (name "unconnected-(U8-NC-Pad14)") (class "Default")
      (node (ref "U8") (pin "14") (pinfunction "NC_14") (pintype "passive+no_connect"))
    )
    (net (code "113") (name "unconnected-(U8-NC-Pad15)") (class "Default")
      (node (ref "U8") (pin "15") (pinfunction "NC_15") (pintype "passive+no_connect"))
    )
    (net (code "114") (name "unconnected-(U8-NC-Pad16)") (class "Default")
      (node (ref "U8") (pin "16") (pinfunction "NC_16") (pintype "passive+no_connect"))
    )
    (net (code "115") (name "unconnected-(U8-NC-Pad17)") (class "Default")
      (node (ref "U8") (pin "17") (pinfunction "NC_17") (pintype "passive+no_connect"))
    )
    (net (code "116") (name "unconnected-(U8-NC-Pad19)") (class "Default")
      (node (ref "U8") (pin "19") (pinfunction "NC_19") (pintype "passive+no_connect"))
    )
    (net (code "117") (name "unconnected-(U8-NC-Pad20)") (class "Default")
      (node (ref "U8") (pin "20") (pinfunction "NC_20") (pintype "passive+no_connect"))
    )
    (net (code "118") (name "unconnected-(U8-NC-Pad21)") (class "Default")
      (node (ref "U8") (pin "21") (pinfunction "NC_21") (pintype "passive+no_connect"))
    )
    (net (code "119") (name "unconnected-(U8-NC-Pad22)") (class "Default")
      (node (ref "U8") (pin "22") (pinfunction "NC_22") (pintype "passive+no_connect"))
    )
    (net (code "120") (name "unconnected-(U8-RI-Pad2)") (class "Default")
      (node (ref "U8") (pin "2") (pinfunction "RI_2") (pintype "passive+no_connect"))
    )
    (net (code "121") (name "unconnected-(U8-SUSPEND#-Pad11)") (class "Default")
      (node (ref "U8") (pin "11") (pinfunction "SUSPEND#_11") (pintype "passive+no_connect"))
    )
    (net (code "122") (name "unconnected-(U8-SUSPEND-Pad12)") (class "Default")
      (node (ref "U8") (pin "12") (pinfunction "SUSPEND_12") (pintype "passive+no_connect"))
    )
  )
)
